# Mech_Interface_Port.net
KiCad netlist of a schematic drawn in Altium Designer
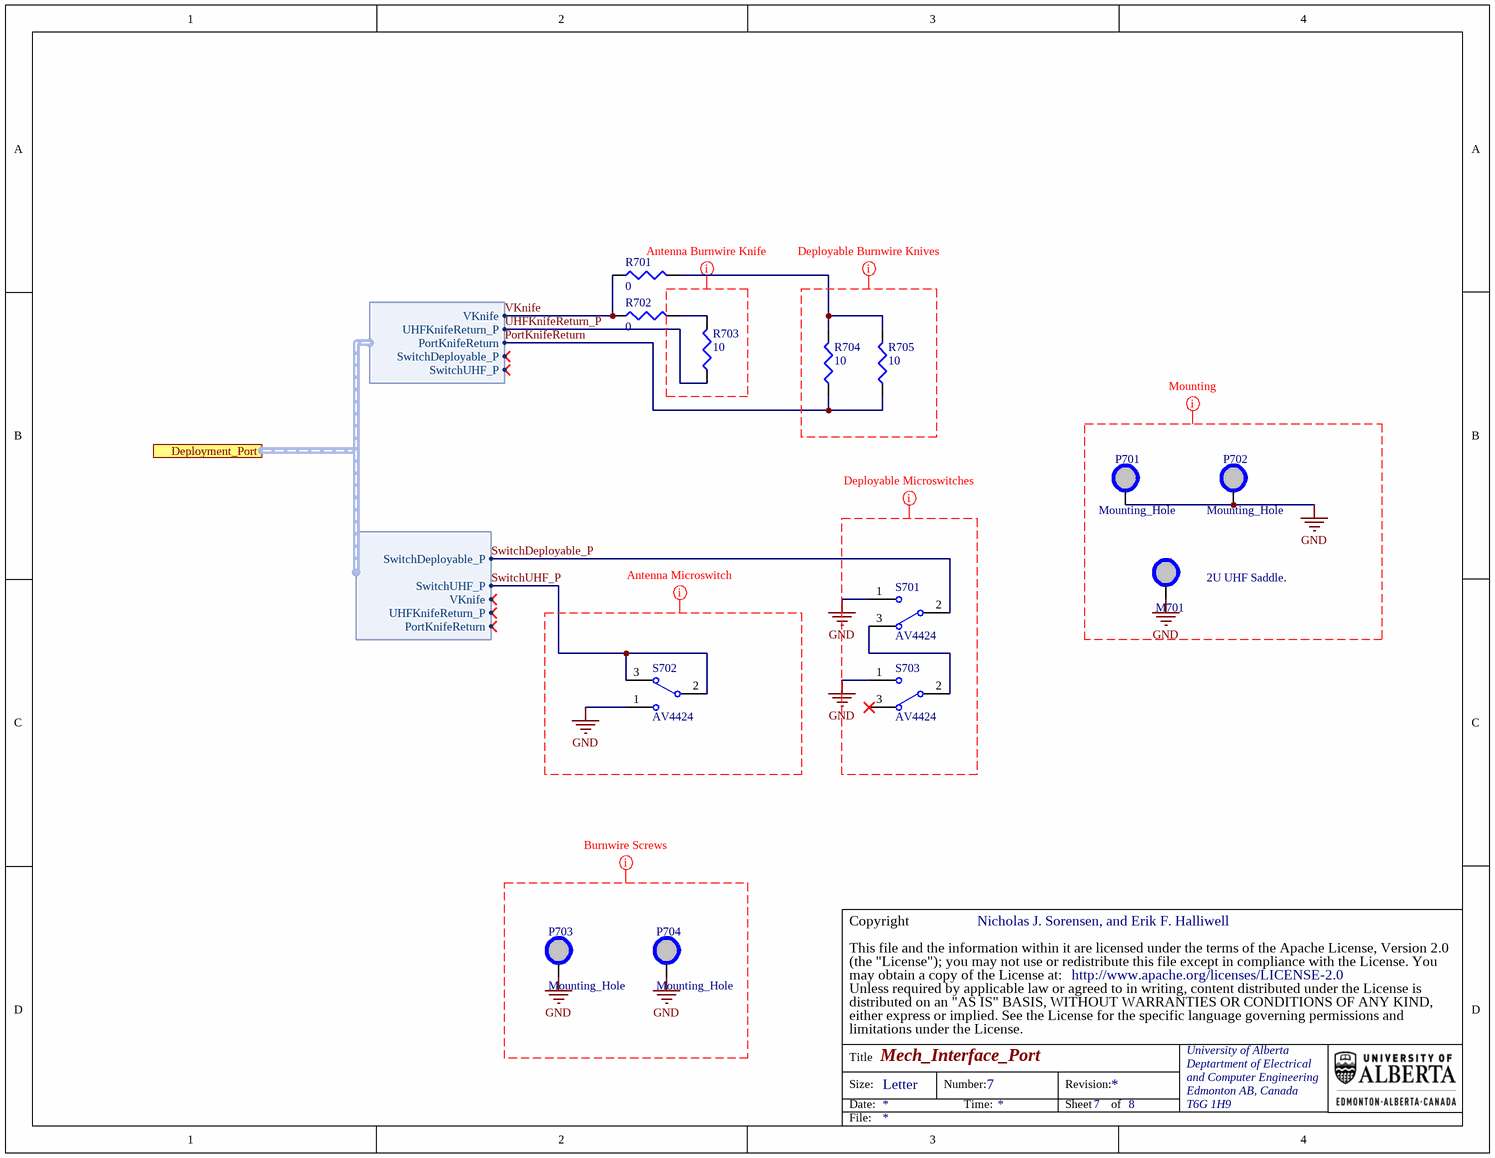
[diagram p0: Mech_Interface_Port.SchDoc]

(export (version "E")
  (design (tool "Eeschema 10.0.6"))
  (components
    (comp (ref "M701")
      (value "2U UHF Saddle.")
      (footprint "2U_ANTENNA_SADDLE")
      (description "Saddle for the UHF antennas to be seated in.")
      (fields
        (field (name "PART NUMBER") "PXX-ABS-00012")
        (field (name "MANUFACTURER PART NUMBER") "Custom")
        (field (name "PUBLISHER") "AlbertaSat")
      )
      (libsource (lib "Database") (part "Mounting_Hole"))
    )
    (comp (ref "P701")
      (value "Mounting_Hole")
      (footprint "DEPHINGE_MOUNTING_HOLE_BODY")
      (fields
        (field (name "PART NUMBER") "PXX-ABS-00004")
        (field (name "MANUFACTURER PART NUMBER") "Custom")
        (field (name "PUBLISHER") "AlbertaSat")
      )
      (libsource (lib "Database") (part "Mounting_Hole"))
    )
    (comp (ref "P702")
      (value "Mounting_Hole")
      (footprint "DEPHINGE_MOUNTING_HOLE_BODY")
      (fields
        (field (name "PART NUMBER") "PXX-ABS-00004")
        (field (name "MANUFACTURER PART NUMBER") "Custom")
        (field (name "PUBLISHER") "AlbertaSat")
      )
      (libsource (lib "Database") (part "Mounting_Hole"))
    )
    (comp (ref "P703")
      (value "Mounting_Hole")
      (footprint "Burnwire_Screw")
      (fields
        (field (name "PART NUMBER") "PXX-ABS-00015")
        (field (name "MANUFACTURER PART NUMBER") "Custom")
        (field (name "PUBLISHER") "AlbertaSat")
      )
      (libsource (lib "Database") (part "Mounting_Hole"))
    )
    (comp (ref "P704")
      (value "Mounting_Hole")
      (footprint "Burnwire_Screw")
      (fields
        (field (name "PART NUMBER") "PXX-ABS-00015")
        (field (name "MANUFACTURER PART NUMBER") "Custom")
        (field (name "PUBLISHER") "AlbertaSat")
      )
      (libsource (lib "Database") (part "Mounting_Hole"))
    )
    (comp (ref "R701")
      (value "0")
      (footprint "PANA-ERJ3G")
      (description "RES SMD 0.0OHM JUMPER 1/10W 0603")
      (fields (field (name "PART NUMBER") "13128") (field (name "MANUFACTURER PART NUMBER") "ERJ-3GEY0R00V"))
      (libsource (lib "Database") (part "Jumper3"))
    )
    (comp (ref "R702")
      (value "0")
      (footprint "PANA-ERJ3G")
      (description "RES SMD 0.0OHM JUMPER 1/10W 0603")
      (fields (field (name "PART NUMBER") "13128") (field (name "MANUFACTURER PART NUMBER") "ERJ-3GEY0R00V"))
      (libsource (lib "Database") (part "Jumper3"))
    )
    (comp (ref "R703")
      (value "10")
      (footprint "VSH-CPF1")
      (description "21 Ohms ±1% 1W Through Hole Resistor Axial Flame Proof, Moisture Resistant, Safety Metal Film")
      (fields
        (field (name "PART NUMBER") "PR-VSH-00317")
        (field (name "MANUFACTURER PART NUMBER") "CPF121R000FKEE6")
        (field (name "PUBLISHER") "AlbertaSat")
      )
      (libsource (lib "Database") (part "Res3"))
    )
    (comp (ref "R704")
      (value "10")
      (footprint "VSH-CPF1")
      (description "21 Ohms ±1% 1W Through Hole Resistor Axial Flame Proof, Moisture Resistant, Safety Metal Film")
      (fields
        (field (name "PART NUMBER") "PR-VSH-00317")
        (field (name "MANUFACTURER PART NUMBER") "CPF121R000FKEE6")
        (field (name "PUBLISHER") "AlbertaSat")
      )
      (libsource (lib "Database") (part "Res3"))
    )
    (comp (ref "R705")
      (value "10")
      (footprint "VSH-CPF1")
      (description "21 Ohms ±1% 1W Through Hole Resistor Axial Flame Proof, Moisture Resistant, Safety Metal Film")
      (fields
        (field (name "PART NUMBER") "PR-VSH-00317")
        (field (name "MANUFACTURER PART NUMBER") "CPF121R000FKEE6")
        (field (name "PUBLISHER") "AlbertaSat")
      )
      (libsource (lib "Database") (part "Res3"))
    )
    (comp (ref "S701")
      (value "AV4424")
      (footprint "PANA-AV4424")
      (description "SWITCH SNAP ACT SPDT 500MA 30V")
      (fields (field (name "PART NUMBER") "20035"))
      (libsource (lib "Database") (part "SW-SPDT"))
    )
    (comp (ref "S702")
      (value "AV4424")
      (footprint "PANA-AV4424")
      (description "SWITCH SNAP ACT SPDT 500MA 30V")
      (fields (field (name "PART NUMBER") "20035"))
      (libsource (lib "Database") (part "SW-SPDT"))
    )
    (comp (ref "S703")
      (value "AV4424")
      (footprint "PANA-AV4424")
      (description "SWITCH SNAP ACT SPDT 500MA 30V")
      (fields (field (name "PART NUMBER") "20035"))
      (libsource (lib "Database") (part "SW-SPDT"))
    )
  )
  (nets
    (net (code "2") (name "/PortKnifeReturn") (class "Default")
      (node (ref "R704") (pin "1") (pinfunction "1_1") (pintype "passive"))
      (node (ref "R705") (pin "1") (pinfunction "1_1") (pintype "passive"))
    )
    (net (code "3") (name "/SwitchDeployable_P") (class "Default")
      (node (ref "S701") (pin "2") (pinfunction "COM_2") (pintype "passive"))
    )
    (net (code "4") (name "/SwitchUHF_P") (class "Default")
      (node (ref "S702") (pin "2") (pinfunction "COM_2") (pintype "passive"))
      (node (ref "S702") (pin "3") (pinfunction "NC_3") (pintype "passive"))
    )
    (net (code "5") (name "/UHFKnifeReturn_P") (class "Default")
      (node (ref "R703") (pin "1") (pinfunction "1_1") (pintype "passive"))
    )
    (net (code "6") (name "/VKnife") (class "Default")
      (node (ref "R701") (pin "1") (pinfunction "1_1") (pintype "passive"))
      (node (ref "R702") (pin "1") (pinfunction "1_1") (pintype "passive"))
    )
    (net (code "8") (name "GND") (class "Default")
      (node (ref "M701") (pin "1") (pinfunction "0_1") (pintype "passive"))
      (node (ref "P701") (pin "1") (pinfunction "0_1") (pintype "passive"))
      (node (ref "P702") (pin "1") (pinfunction "0_1") (pintype "passive"))
      (node (ref "P703") (pin "1") (pinfunction "0_1") (pintype "passive"))
      (node (ref "P704") (pin "1") (pinfunction "0_1") (pintype "passive"))
      (node (ref "S701") (pin "1") (pinfunction "NO_1") (pintype "passive"))
      (node (ref "S702") (pin "1") (pinfunction "NO_1") (pintype "passive"))
      (node (ref "S703") (pin "1") (pinfunction "NO_1") (pintype "passive"))
    )
    (net (code "9") (name "Net-(R701-Pad2)") (class "Default")
      (node (ref "R701") (pin "2") (pinfunction "2_2") (pintype "passive"))
      (node (ref "R704") (pin "2") (pinfunction "2_2") (pintype "passive"))
      (node (ref "R705") (pin "2") (pinfunction "2_2") (pintype "passive"))
    )
    (net (code "10") (name "Net-(R702-Pad2)") (class "Default")
      (node (ref "R702") (pin "2") (pinfunction "2_2") (pintype "passive"))
      (node (ref "R703") (pin "2") (pinfunction "2_2") (pintype "passive"))
    )
    (net (code "11") (name "Net-(S701-NC)") (class "Default")
      (node (ref "S701") (pin "3") (pinfunction "NC_3") (pintype "passive"))
      (node (ref "S703") (pin "2") (pinfunction "COM_2") (pintype "passive"))
    )
    (net (code "12") (name "unconnected-(S703-NC-Pad3)") (class "Default")
      (node (ref "S703") (pin "3") (pinfunction "NC_3") (pintype "passive+no_connect"))
    )
  )
)
